# DIOT_template.net
KiCad netlist of a schematic drawn in Altium Designer
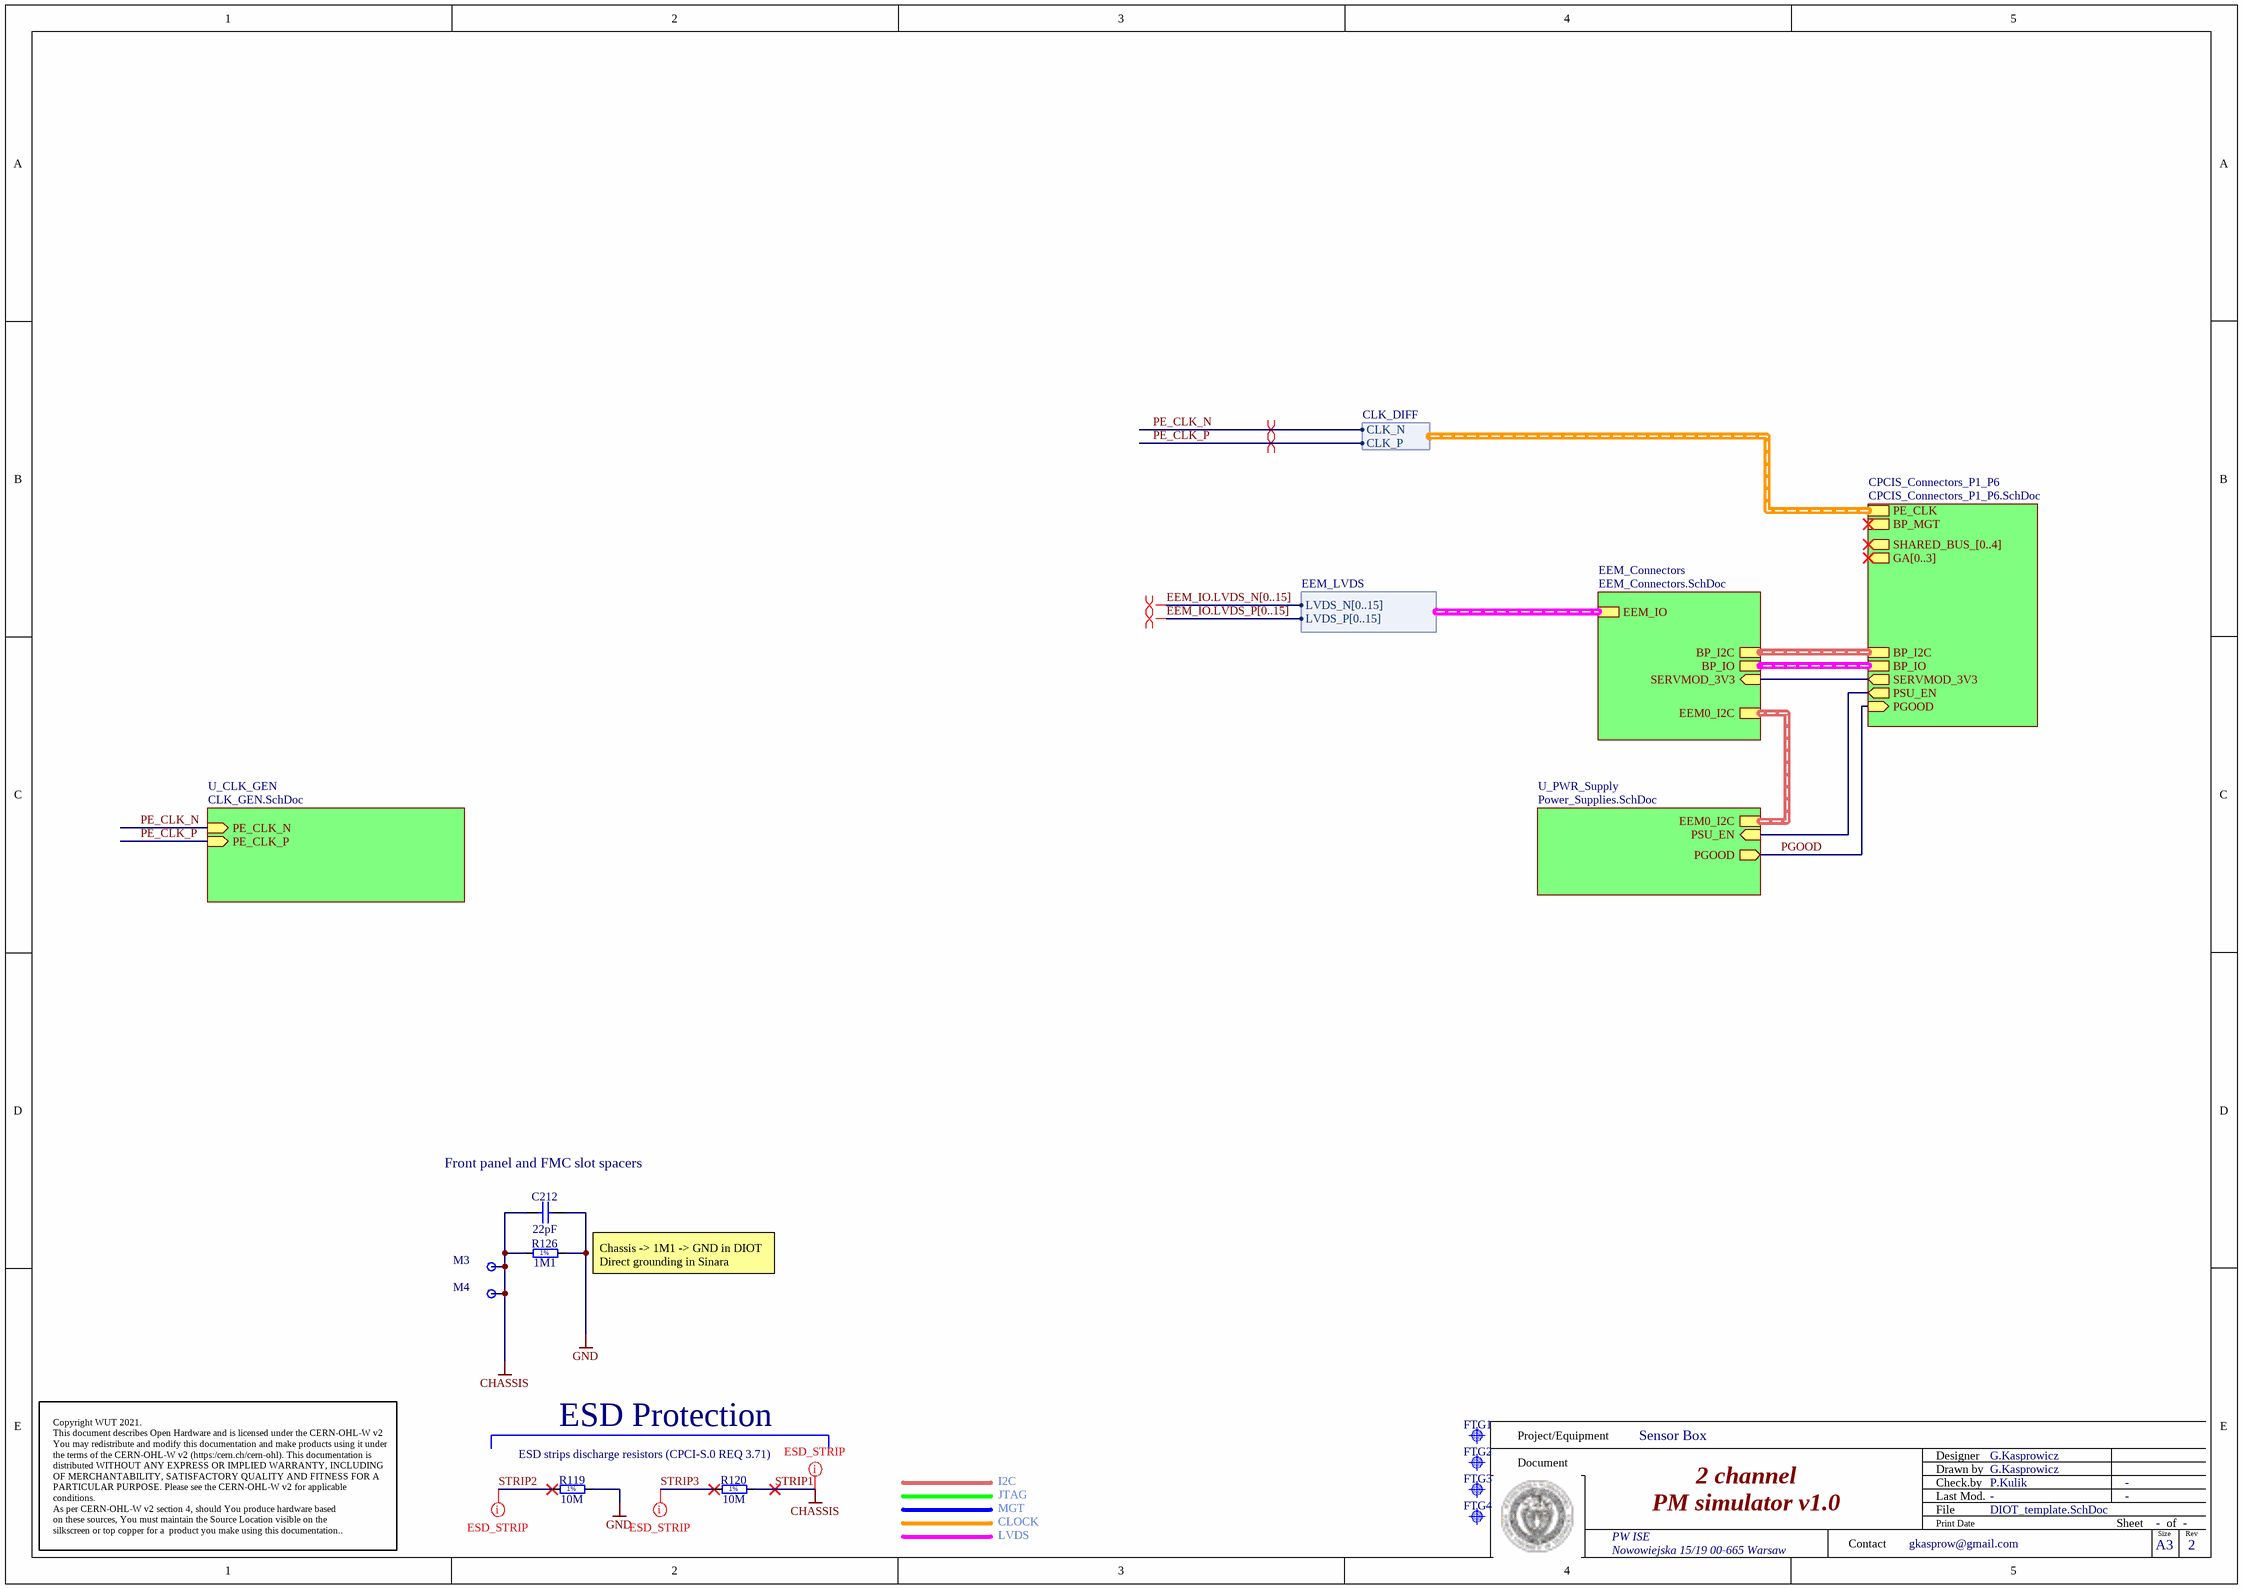
[diagram p0: DIOT_template.SchDoc]

(export (version "E")
  (design (tool "Eeschema 10.0.6"))
  (components
    (comp (ref "C212")
      (value "22pF")
      (footprint "CAPC1005X55N")
      (description "Non-polarised capacitor")
      (fields
        (field (name "PART NUMBER") "CC0402_22PF_50V_5%_C0G")
        (field (name "VOLTAGE") "50V")
        (field (name "AUTHOR") "CERN DEM JLC")
      )
      (libsource (lib "Capacitors") (part "Capacitor - non polarized"))
    )
    (comp (ref "FTG1")
      (value "Use only in PCB")
      (footprint "FIDUCIAL_TOP_C100-200")
      (description "Fiducial Target")
      (fields (field (name "PART NUMBER") "FIDUCIAL_TARGET_C100-200") (field (name "AUTHOR") "CERN DEM JLC"))
      (libsource (lib "Eletro-mechanical") (part "Fiducial Target"))
    )
    (comp (ref "FTG2")
      (value "Use only in PCB")
      (footprint "FIDUCIAL_TOP_S100-200")
      (description "Fiducial Target")
      (fields (field (name "PART NUMBER") "FIDUCIAL_TARGET_S100-200") (field (name "AUTHOR") "CERN DEM JLC"))
      (libsource (lib "Eletro-mechanical") (part "Fiducial Target"))
    )
    (comp (ref "FTG3")
      (value "Use only in PCB")
      (footprint "FIDUCIAL_TOP_S100-200")
      (description "Fiducial Target")
      (fields (field (name "PART NUMBER") "FIDUCIAL_TARGET_S100-200") (field (name "AUTHOR") "CERN DEM JLC"))
      (libsource (lib "Eletro-mechanical") (part "Fiducial Target"))
    )
    (comp (ref "FTG4")
      (value "Use only in PCB")
      (footprint "FIDUCIAL_TOP_S100-200")
      (description "Fiducial Target")
      (fields (field (name "PART NUMBER") "FIDUCIAL_TARGET_S100-200") (field (name "AUTHOR") "CERN DEM JLC"))
      (libsource (lib "Eletro-mechanical") (part "Fiducial Target"))
    )
    (comp (ref "M3")
      (value "Plated Hole")
      (footprint "MTG300_600")
      (description "Single Terminal Socket")
      (fields (field (name "PART NUMBER") "PLATED_HOLE3.0_PAD6.0") (field (name "AUTHOR") "CERN DEM JLC"))
      (libsource (lib "Eletro-mechanical") (part "Single Terminal Socket"))
    )
    (comp (ref "M4")
      (value "Plated Hole")
      (footprint "MTG300_600")
      (description "Single Terminal Socket")
      (fields (field (name "PART NUMBER") "PLATED_HOLE3.0_PAD6.0") (field (name "AUTHOR") "CERN DEM JLC"))
      (libsource (lib "Eletro-mechanical") (part "Single Terminal Socket"))
    )
    (comp (ref "R119")
      (value "10M")
      (footprint "RESC2113X55N")
      (description "Resistor - 1%")
      (fields
        (field (name "PART NUMBER") "R0805_10M_1%_0.125W_100PPM_VISHAY_CRCW e3")
        (field (name "POWER") "0.125W")
        (field (name "AUTHOR") "CERN DEM BC")
      )
      (libsource (lib "Resistors") (part "Resistor - 1%"))
    )
    (comp (ref "R120")
      (value "10M")
      (footprint "RESC2113X55N")
      (description "Resistor - 1%")
      (fields
        (field (name "PART NUMBER") "R0805_10M_1%_0.125W_100PPM_VISHAY_CRCW e3")
        (field (name "POWER") "0.125W")
        (field (name "AUTHOR") "CERN DEM BC")
      )
      (libsource (lib "Resistors") (part "Resistor - 1%"))
    )
    (comp (ref "R126")
      (value "1M1")
      (footprint "RESC2012X60N")
      (description "Resistor - 1%")
      (fields
        (field (name "PART NUMBER") "R0805_1M1_1%_0.125W_100PPM")
        (field (name "MANUFACTURER") "GENERIC")
        (field (name "AUTHOR") "CERN DEM JLC")
      )
      (libsource (lib "Resistors") (part "Resistor - 1%"))
    )
  )
  (nets
    (net (code "32") (name "/STRIP2") (class "Default")
      (node (ref "R119") (pin "1") (pinfunction "1_1") (pintype "passive+no_connect"))
    )
    (net (code "33") (name "/STRIP3") (class "Default")
      (node (ref "R120") (pin "1") (pinfunction "1_1") (pintype "passive+no_connect"))
    )
    (net (code "35") (name "CHASSIS") (class "Default")
      (node (ref "C212") (pin "1") (pinfunction "1_1") (pintype "passive"))
      (node (ref "M3") (pin "1") (pinfunction "1_1") (pintype "bidirectional"))
      (node (ref "M4") (pin "1") (pinfunction "1_1") (pintype "bidirectional"))
      (node (ref "R120") (pin "2") (pinfunction "2_2") (pintype "passive"))
      (node (ref "R126") (pin "1") (pinfunction "1_1") (pintype "passive"))
    )
    (net (code "36") (name "GND") (class "Default")
      (node (ref "C212") (pin "2") (pinfunction "2_2") (pintype "passive"))
      (node (ref "R119") (pin "2") (pinfunction "2_2") (pintype "passive"))
      (node (ref "R126") (pin "2") (pinfunction "2_2") (pintype "passive"))
    )
  )
)
